# LPCB219_-_NODE_CORE.net
KiCad netlist of a schematic drawn in Altium Designer
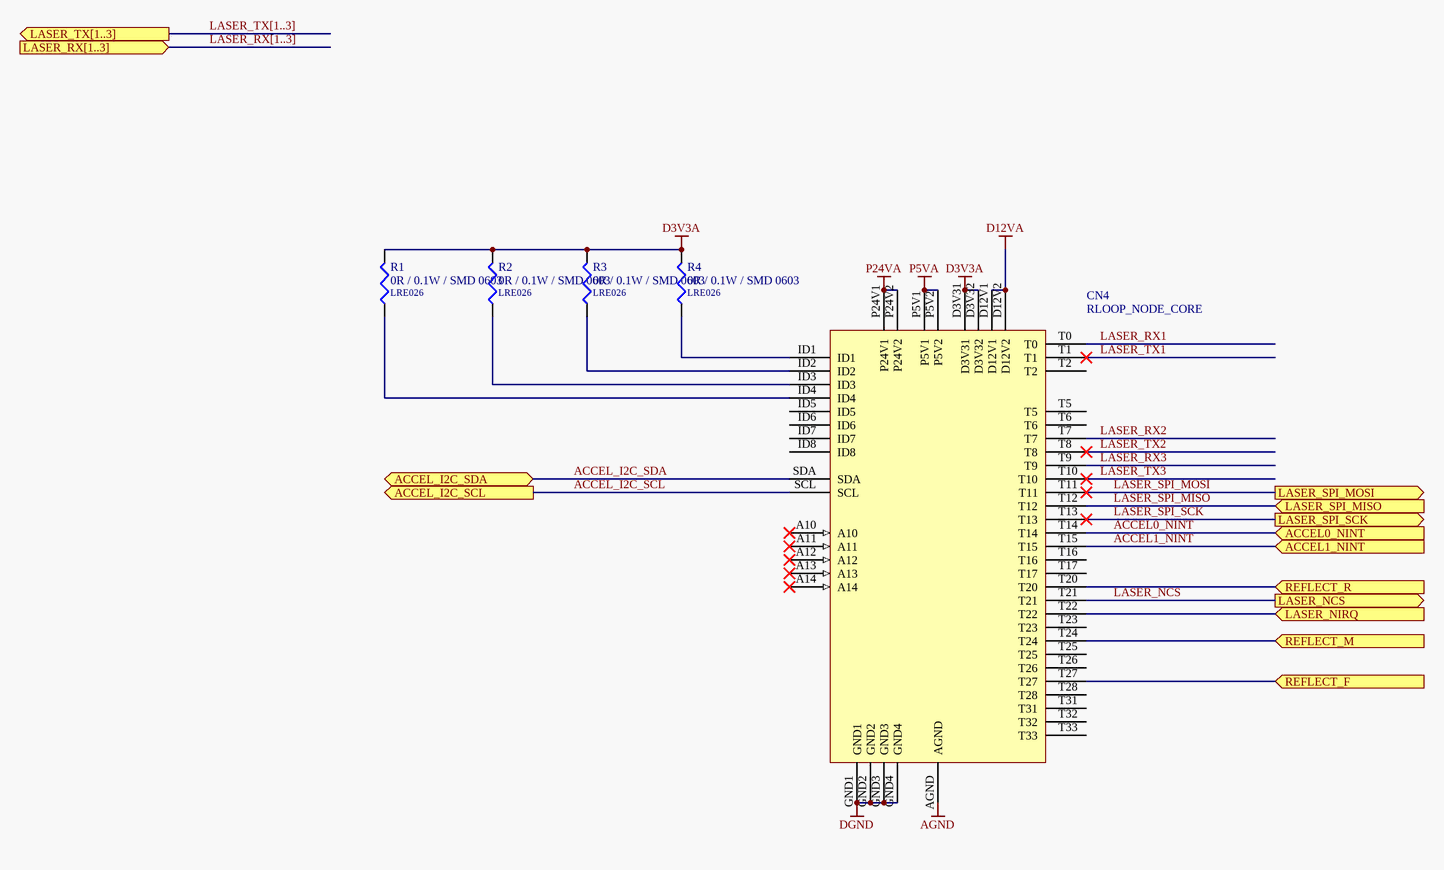
[diagram p0: LPCB219 - NODE CORE.SchDoc]

(export (version "E")
  (design (tool "Eeschema 10.0.6"))
  (components
    (comp (ref "CN4")
      (value "RLOOP_NODE_CORE")
      (footprint "RLOOP_NODE_CORE")
      (description "rLoop Node Core Connector")
      (libsource (lib "LDL_Connectors") (part "RLOOP_NODE_CORE"))
    )
    (comp (ref "R1")
      (value "0R / 0.1W / SMD 0603")
      (footprint "LFP020__CR1608-0603-IPC7351_B")
      (description "Resistor, Ceramic Chip, 0R, 0.1W, SMD 0603 [LRE026]")
      (fields (field (name "LDL_NUMBER") "LRE026"))
      (libsource (lib "LDL_Resistors") (part "0R / 0.1W / SMD 0603"))
    )
    (comp (ref "R2")
      (value "0R / 0.1W / SMD 0603")
      (footprint "LFP020__CR1608-0603-IPC7351_B")
      (description "Resistor, Ceramic Chip, 0R, 0.1W, SMD 0603 [LRE026]")
      (fields (field (name "LDL_NUMBER") "LRE026"))
      (libsource (lib "LDL_Resistors") (part "0R / 0.1W / SMD 0603"))
    )
    (comp (ref "R3")
      (value "0R / 0.1W / SMD 0603")
      (footprint "LFP020__CR1608-0603-IPC7351_B")
      (description "Resistor, Ceramic Chip, 0R, 0.1W, SMD 0603 [LRE026]")
      (fields (field (name "LDL_NUMBER") "LRE026"))
      (libsource (lib "LDL_Resistors") (part "0R / 0.1W / SMD 0603"))
    )
    (comp (ref "R4")
      (value "0R / 0.1W / SMD 0603")
      (footprint "LFP020__CR1608-0603-IPC7351_B")
      (description "Resistor, Ceramic Chip, 0R, 0.1W, SMD 0603 [LRE026]")
      (fields (field (name "LDL_NUMBER") "LRE026"))
      (libsource (lib "LDL_Resistors") (part "0R / 0.1W / SMD 0603"))
    )
  )
  (nets
    (net (code "1") (name "/ACCEL0_NINT") (class "Default")
      (node (ref "CN4") (pin "T14") (pinfunction "T14_T14") (pintype "passive"))
    )
    (net (code "2") (name "/ACCEL1_NINT") (class "Default")
      (node (ref "CN4") (pin "T15") (pinfunction "T15_T15") (pintype "passive"))
    )
    (net (code "3") (name "/ACCEL_I2C_SCL") (class "Default")
      (node (ref "CN4") (pin "SCL") (pinfunction "SCL_SCL") (pintype "passive"))
    )
    (net (code "4") (name "/ACCEL_I2C_SDA") (class "Default")
      (node (ref "CN4") (pin "SDA") (pinfunction "SDA_SDA") (pintype "passive"))
    )
    (net (code "5") (name "/LASER_NCS") (class "Default")
      (node (ref "CN4") (pin "T21") (pinfunction "T21_T21") (pintype "passive"))
    )
    (net (code "6") (name "/LASER_NIRQ") (class "Default")
      (node (ref "CN4") (pin "T22") (pinfunction "T22_T22") (pintype "passive"))
    )
    (net (code "7") (name "/LASER_RX1") (class "Default")
      (node (ref "CN4") (pin "T0") (pinfunction "T0_T0") (pintype "passive"))
    )
    (net (code "8") (name "/LASER_RX2") (class "Default")
      (node (ref "CN4") (pin "T7") (pinfunction "T7_T7") (pintype "passive"))
    )
    (net (code "9") (name "/LASER_RX3") (class "Default")
      (node (ref "CN4") (pin "T9") (pinfunction "T9_T9") (pintype "passive"))
    )
    (net (code "11") (name "/LASER_SPI_MISO") (class "Default")
      (node (ref "CN4") (pin "T12") (pinfunction "T12_T12") (pintype "passive"))
    )
    (net (code "12") (name "/LASER_SPI_MOSI") (class "Default")
      (node (ref "CN4") (pin "T11") (pinfunction "T11_T11") (pintype "passive+no_connect"))
    )
    (net (code "13") (name "/LASER_SPI_SCK") (class "Default")
      (node (ref "CN4") (pin "T13") (pinfunction "T13_T13") (pintype "passive+no_connect"))
    )
    (net (code "14") (name "/LASER_TX1") (class "Default")
      (node (ref "CN4") (pin "T1") (pinfunction "T1_T1") (pintype "passive+no_connect"))
    )
    (net (code "15") (name "/LASER_TX2") (class "Default")
      (node (ref "CN4") (pin "T8") (pinfunction "T8_T8") (pintype "passive+no_connect"))
    )
    (net (code "16") (name "/LASER_TX3") (class "Default")
      (node (ref "CN4") (pin "T10") (pinfunction "T10_T10") (pintype "passive+no_connect"))
    )
    (net (code "18") (name "/REFLECT_F") (class "Default")
      (node (ref "CN4") (pin "T27") (pinfunction "T27_T27") (pintype "passive"))
    )
    (net (code "19") (name "/REFLECT_M") (class "Default")
      (node (ref "CN4") (pin "T24") (pinfunction "T24_T24") (pintype "passive"))
    )
    (net (code "20") (name "/REFLECT_R") (class "Default")
      (node (ref "CN4") (pin "T20") (pinfunction "T20_T20") (pintype "passive"))
    )
    (net (code "21") (name "AGND") (class "Default")
      (node (ref "CN4") (pin "AGND") (pinfunction "AGND_AGND") (pintype "power_in"))
    )
    (net (code "22") (name "D3V3A") (class "Default")
      (node (ref "CN4") (pin "D3V31") (pinfunction "D3V31_D3V31") (pintype "power_in"))
      (node (ref "CN4") (pin "D3V32") (pinfunction "D3V32_D3V32") (pintype "power_in"))
      (node (ref "R1") (pin "2") (pintype "passive"))
      (node (ref "R2") (pin "2") (pintype "passive"))
      (node (ref "R3") (pin "2") (pintype "passive"))
      (node (ref "R4") (pin "2") (pintype "passive"))
    )
    (net (code "23") (name "D12VA") (class "Default")
      (node (ref "CN4") (pin "D12V1") (pinfunction "D12V1_D12V1") (pintype "power_in"))
      (node (ref "CN4") (pin "D12V2") (pinfunction "D12V2_D12V2") (pintype "power_in"))
    )
    (net (code "24") (name "DGND") (class "Default")
      (node (ref "CN4") (pin "GND1") (pinfunction "GND1_GND1") (pintype "power_in"))
      (node (ref "CN4") (pin "GND2") (pinfunction "GND2_GND2") (pintype "power_in"))
      (node (ref "CN4") (pin "GND3") (pinfunction "GND3_GND3") (pintype "power_in"))
      (node (ref "CN4") (pin "GND4") (pinfunction "GND4_GND4") (pintype "power_in"))
    )
    (net (code "25") (name "Net-(CN4-PadID1)") (class "Default")
      (node (ref "CN4") (pin "ID1") (pinfunction "ID1_ID1") (pintype "passive"))
      (node (ref "R4") (pin "1") (pintype "passive"))
    )
    (net (code "26") (name "Net-(CN4-PadID2)") (class "Default")
      (node (ref "CN4") (pin "ID2") (pinfunction "ID2_ID2") (pintype "passive"))
      (node (ref "R3") (pin "1") (pintype "passive"))
    )
    (net (code "27") (name "Net-(CN4-PadID3)") (class "Default")
      (node (ref "CN4") (pin "ID3") (pinfunction "ID3_ID3") (pintype "passive"))
      (node (ref "R2") (pin "1") (pintype "passive"))
    )
    (net (code "28") (name "Net-(CN4-PadID4)") (class "Default")
      (node (ref "CN4") (pin "ID4") (pinfunction "ID4_ID4") (pintype "passive"))
      (node (ref "R1") (pin "1") (pintype "passive"))
    )
    (net (code "29") (name "P5VA") (class "Default")
      (node (ref "CN4") (pin "P5V1") (pinfunction "P5V1_P5V1") (pintype "power_in"))
      (node (ref "CN4") (pin "P5V2") (pinfunction "P5V2_P5V2") (pintype "power_in"))
    )
    (net (code "30") (name "P24VA") (class "Default")
      (node (ref "CN4") (pin "P24V1") (pinfunction "P24V1_P24V1") (pintype "power_in"))
      (node (ref "CN4") (pin "P24V2") (pinfunction "P24V2_P24V2") (pintype "power_in"))
    )
    (net (code "31") (name "unconnected-(CN4-PadA10)") (class "Default")
      (node (ref "CN4") (pin "A10") (pinfunction "A10_A10") (pintype "input+no_connect"))
    )
    (net (code "32") (name "unconnected-(CN4-PadA11)") (class "Default")
      (node (ref "CN4") (pin "A11") (pinfunction "A11_A11") (pintype "input+no_connect"))
    )
    (net (code "33") (name "unconnected-(CN4-PadA12)") (class "Default")
      (node (ref "CN4") (pin "A12") (pinfunction "A12_A12") (pintype "input+no_connect"))
    )
    (net (code "34") (name "unconnected-(CN4-PadA13)") (class "Default")
      (node (ref "CN4") (pin "A13") (pinfunction "A13_A13") (pintype "input+no_connect"))
    )
    (net (code "35") (name "unconnected-(CN4-PadA14)") (class "Default")
      (node (ref "CN4") (pin "A14") (pinfunction "A14_A14") (pintype "input+no_connect"))
    )
    (net (code "36") (name "unconnected-(CN4-PadID5)") (class "Default")
      (node (ref "CN4") (pin "ID5") (pinfunction "ID5_ID5") (pintype "passive"))
    )
    (net (code "37") (name "unconnected-(CN4-PadID6)") (class "Default")
      (node (ref "CN4") (pin "ID6") (pinfunction "ID6_ID6") (pintype "passive"))
    )
    (net (code "38") (name "unconnected-(CN4-PadID7)") (class "Default")
      (node (ref "CN4") (pin "ID7") (pinfunction "ID7_ID7") (pintype "passive"))
    )
    (net (code "39") (name "unconnected-(CN4-PadID8)") (class "Default")
      (node (ref "CN4") (pin "ID8") (pinfunction "ID8_ID8") (pintype "passive"))
    )
    (net (code "40") (name "unconnected-(CN4-PadT2)") (class "Default")
      (node (ref "CN4") (pin "T2") (pinfunction "T2_T2") (pintype "passive"))
    )
    (net (code "41") (name "unconnected-(CN4-PadT5)") (class "Default")
      (node (ref "CN4") (pin "T5") (pinfunction "T5_T5") (pintype "passive"))
    )
    (net (code "42") (name "unconnected-(CN4-PadT6)") (class "Default")
      (node (ref "CN4") (pin "T6") (pinfunction "T6_T6") (pintype "passive"))
    )
    (net (code "43") (name "unconnected-(CN4-PadT16)") (class "Default")
      (node (ref "CN4") (pin "T16") (pinfunction "T16_T16") (pintype "passive"))
    )
    (net (code "44") (name "unconnected-(CN4-PadT17)") (class "Default")
      (node (ref "CN4") (pin "T17") (pinfunction "T17_T17") (pintype "passive"))
    )
    (net (code "45") (name "unconnected-(CN4-PadT23)") (class "Default")
      (node (ref "CN4") (pin "T23") (pinfunction "T23_T23") (pintype "passive"))
    )
    (net (code "46") (name "unconnected-(CN4-PadT25)") (class "Default")
      (node (ref "CN4") (pin "T25") (pinfunction "T25_T25") (pintype "passive"))
    )
    (net (code "47") (name "unconnected-(CN4-PadT26)") (class "Default")
      (node (ref "CN4") (pin "T26") (pinfunction "T26_T26") (pintype "passive"))
    )
    (net (code "48") (name "unconnected-(CN4-PadT28)") (class "Default")
      (node (ref "CN4") (pin "T28") (pinfunction "T28_T28") (pintype "passive"))
    )
    (net (code "49") (name "unconnected-(CN4-PadT31)") (class "Default")
      (node (ref "CN4") (pin "T31") (pinfunction "T31_T31") (pintype "passive"))
    )
    (net (code "50") (name "unconnected-(CN4-PadT32)") (class "Default")
      (node (ref "CN4") (pin "T32") (pinfunction "T32_T32") (pintype "passive"))
    )
    (net (code "51") (name "unconnected-(CN4-PadT33)") (class "Default")
      (node (ref "CN4") (pin "T33") (pinfunction "T33_T33") (pintype "passive"))
    )
  )
)
